# Laser_Teensy4save.net
KiCad netlist of a schematic drawn in EAGLE
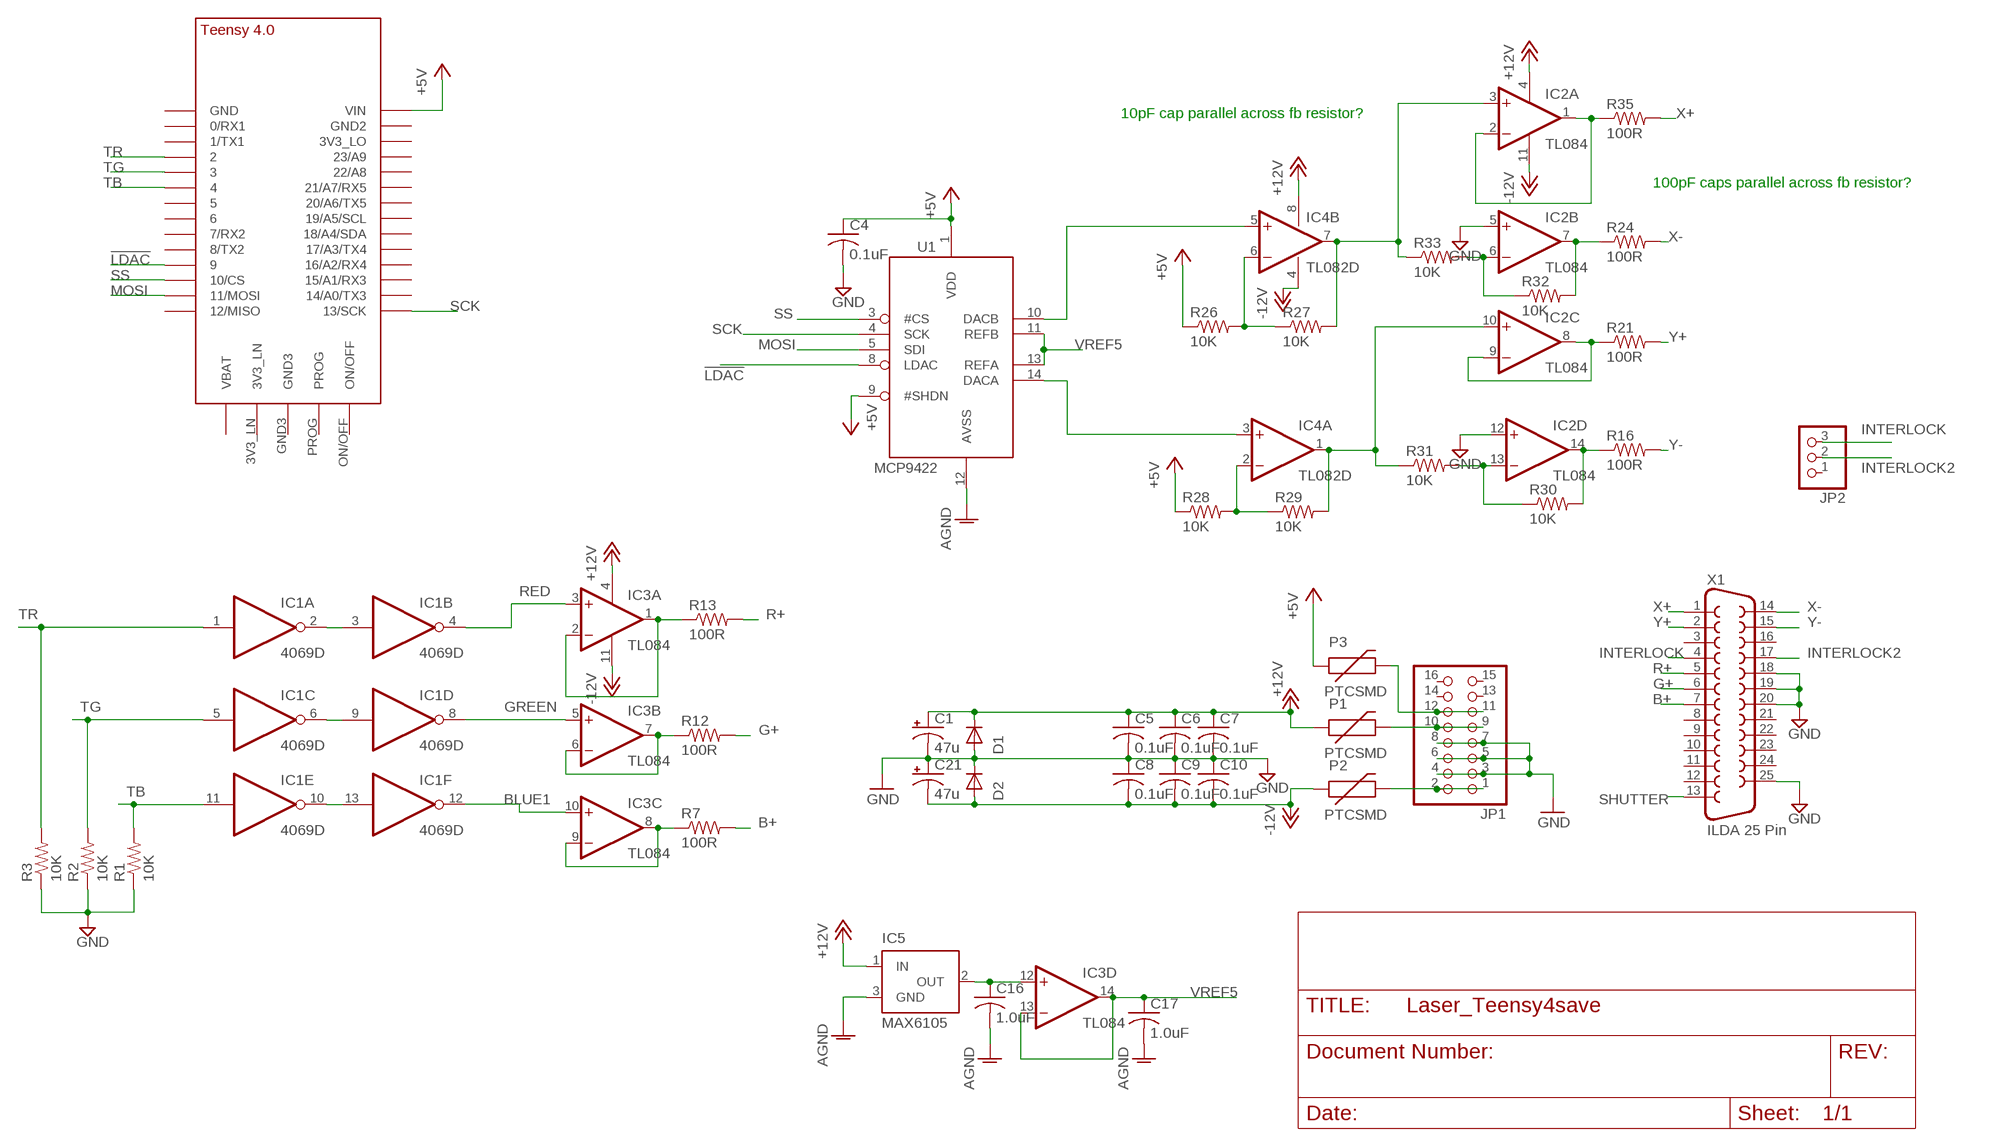
[diagram p0: schematic, sheet 1]

(export (version "E")
  (design (tool "Eeschema 10.0.6"))
  (components
    (comp (ref "C1")
      (value "47u")
      (footprint "eagle-import:PANASONIC_D")
      (libsource (lib "eagle-import") (part "CPOL-USD"))
    )
    (comp (ref "C4")
      (value "0.1uF")
      (footprint "eagle-import:C0603")
      (libsource (lib "eagle-import") (part "C-USC0603"))
    )
    (comp (ref "C5")
      (value "0.1uF")
      (footprint "eagle-import:C0603")
      (libsource (lib "eagle-import") (part "C-USC0603"))
    )
    (comp (ref "C6")
      (value "0.1uF")
      (footprint "eagle-import:C0603")
      (libsource (lib "eagle-import") (part "C-USC0603"))
    )
    (comp (ref "C7")
      (value "0.1uF")
      (footprint "eagle-import:C0603")
      (libsource (lib "eagle-import") (part "C-USC0603"))
    )
    (comp (ref "C8")
      (value "0.1uF")
      (footprint "eagle-import:C0603")
      (libsource (lib "eagle-import") (part "C-USC0603"))
    )
    (comp (ref "C9")
      (value "0.1uF")
      (footprint "eagle-import:C0603")
      (libsource (lib "eagle-import") (part "C-USC0603"))
    )
    (comp (ref "C10")
      (value "0.1uF")
      (footprint "eagle-import:C0603")
      (libsource (lib "eagle-import") (part "C-USC0603"))
    )
    (comp (ref "C16")
      (value "1.0uF")
      (footprint "eagle-import:C025-024X044")
      (libsource (lib "eagle-import") (part "C-US025-024X044"))
    )
    (comp (ref "C17")
      (value "1.0uF")
      (footprint "eagle-import:C025-024X044")
      (libsource (lib "eagle-import") (part "C-US025-024X044"))
    )
    (comp (ref "C21")
      (value "47u")
      (footprint "eagle-import:PANASONIC_D")
      (libsource (lib "eagle-import") (part "CPOL-USD"))
    )
    (comp (ref "D1")
      (value "1N5819HW")
      (footprint "eagle-import:SOD123")
      (libsource (lib "eagle-import") (part "DIODE-SOD123"))
    )
    (comp (ref "D2")
      (value "1N5819HW")
      (footprint "eagle-import:SOD123")
      (libsource (lib "eagle-import") (part "DIODE-SOD123"))
    )
    (comp (ref "IC1")
      (value "4069D")
      (footprint "eagle-import:SO14")
      (libsource (lib "eagle-import") (part "4069D"))
    )
    (comp (ref "IC2")
      (value "TL084")
      (footprint "eagle-import:SOIC-14")
      (libsource (lib "eagle-import") (part "TL084"))
    )
    (comp (ref "IC3")
      (value "TL084")
      (footprint "eagle-import:SOIC-14")
      (libsource (lib "eagle-import") (part "TL084"))
    )
    (comp (ref "IC4")
      (value "TL082D")
      (footprint "eagle-import:SO08")
      (libsource (lib "eagle-import") (part "TL082D"))
    )
    (comp (ref "IC5")
      (value "MAX6105")
      (footprint "eagle-import:SOT23")
      (libsource (lib "eagle-import") (part "MAX6520"))
    )
    (comp (ref "JP1")
      (value "PINHD-2X8")
      (footprint "eagle-import:2X08")
      (libsource (lib "eagle-import") (part "PINHD-2X8"))
    )
    (comp (ref "JP2")
      (value "PINHD-1X3")
      (footprint "eagle-import:1X03")
      (libsource (lib "eagle-import") (part "PINHD-1X3"))
    )
    (comp (ref "P1")
      (value "PTCSMD")
      (footprint "eagle-import:PTC-1206")
      (libsource (lib "eagle-import") (part "PTCSMD"))
    )
    (comp (ref "P2")
      (value "PTCSMD")
      (footprint "eagle-import:PTC-1206")
      (libsource (lib "eagle-import") (part "PTCSMD"))
    )
    (comp (ref "P3")
      (value "PTCSMD")
      (footprint "eagle-import:PTC-1206")
      (libsource (lib "eagle-import") (part "PTCSMD"))
    )
    (comp (ref "R1")
      (value "10K")
      (footprint "eagle-import:R0603")
      (libsource (lib "eagle-import") (part "R-US_R0603"))
    )
    (comp (ref "R2")
      (value "10K")
      (footprint "eagle-import:R0603")
      (libsource (lib "eagle-import") (part "R-US_R0603"))
    )
    (comp (ref "R3")
      (value "10K")
      (footprint "eagle-import:R0603")
      (libsource (lib "eagle-import") (part "R-US_R0603"))
    )
    (comp (ref "R7")
      (value "100R")
      (footprint "eagle-import:R0603")
      (libsource (lib "eagle-import") (part "R-US_R0603"))
    )
    (comp (ref "R12")
      (value "100R")
      (footprint "eagle-import:R0603")
      (libsource (lib "eagle-import") (part "R-US_R0603"))
    )
    (comp (ref "R13")
      (value "100R")
      (footprint "eagle-import:R0603")
      (libsource (lib "eagle-import") (part "R-US_R0603"))
    )
    (comp (ref "R16")
      (value "100R")
      (footprint "eagle-import:R0603")
      (libsource (lib "eagle-import") (part "R-US_R0603"))
    )
    (comp (ref "R21")
      (value "100R")
      (footprint "eagle-import:R0603")
      (libsource (lib "eagle-import") (part "R-US_R0603"))
    )
    (comp (ref "R24")
      (value "100R")
      (footprint "eagle-import:R0603")
      (libsource (lib "eagle-import") (part "R-US_R0603"))
    )
    (comp (ref "R26")
      (value "10K")
      (footprint "eagle-import:R0603")
      (libsource (lib "eagle-import") (part "R-US_R0603"))
    )
    (comp (ref "R27")
      (value "10K")
      (footprint "eagle-import:R0603")
      (libsource (lib "eagle-import") (part "R-US_R0603"))
    )
    (comp (ref "R28")
      (value "10K")
      (footprint "eagle-import:R0603")
      (libsource (lib "eagle-import") (part "R-US_R0603"))
    )
    (comp (ref "R29")
      (value "10K")
      (footprint "eagle-import:R0603")
      (libsource (lib "eagle-import") (part "R-US_R0603"))
    )
    (comp (ref "R30")
      (value "10K")
      (footprint "eagle-import:R0603")
      (libsource (lib "eagle-import") (part "R-US_R0603"))
    )
    (comp (ref "R31")
      (value "10K")
      (footprint "eagle-import:R0603")
      (libsource (lib "eagle-import") (part "R-US_R0603"))
    )
    (comp (ref "R32")
      (value "10K")
      (footprint "eagle-import:R0603")
      (libsource (lib "eagle-import") (part "R-US_R0603"))
    )
    (comp (ref "R33")
      (value "10K")
      (footprint "eagle-import:R0603")
      (libsource (lib "eagle-import") (part "R-US_R0603"))
    )
    (comp (ref "R35")
      (value "100R")
      (footprint "eagle-import:R0603")
      (libsource (lib "eagle-import") (part "R-US_R0603"))
    )
    (comp (ref "U$1")
      (value "TEENSY_4.0")
      (footprint "eagle-import:TEENSY_4.0")
      (libsource (lib "eagle-import") (part "TEENSY_4.0"))
    )
    (comp (ref "U1")
      (value "MCP4922")
      (footprint "eagle-import:SOIC-14")
      (libsource (lib "eagle-import") (part "MCP4922"))
    )
    (comp (ref "X1")
      (value "ILDA 25 Pin")
      (footprint "eagle-import:F25D")
      (libsource (lib "eagle-import") (part "F25D"))
    )
  )
  (nets
    (net (code "1") (name "+5V") (class "Default")
      (node (ref "C4") (pin "1") (pinfunction "1_1") (pintype "passive"))
      (node (ref "P3") (pin "1") (pinfunction "1_1") (pintype "bidirectional"))
      (node (ref "R26") (pin "1") (pinfunction "1_1") (pintype "passive"))
      (node (ref "R28") (pin "1") (pinfunction "1_1") (pintype "passive"))
      (node (ref "U$1") (pin "VIN") (pinfunction "VIN_VIN") (pintype "bidirectional"))
      (node (ref "U1") (pin "1") (pinfunction "VDD_1") (pintype "power_in"))
      (node (ref "U1") (pin "9") (pinfunction "#SHDN_9") (pintype "input"))
    )
    (net (code "2") (name "+12V") (class "Default")
      (node (ref "C1") (pin "+") (pinfunction "+_+") (pintype "passive"))
      (node (ref "C5") (pin "1") (pinfunction "1_1") (pintype "passive"))
      (node (ref "C6") (pin "1") (pinfunction "1_1") (pintype "passive"))
      (node (ref "C7") (pin "1") (pinfunction "1_1") (pintype "passive"))
      (node (ref "D1") (pin "C") (pinfunction "C_C") (pintype "passive"))
      (node (ref "IC2") (pin "4") (pinfunction "V+_4") (pintype "power_in"))
      (node (ref "IC3") (pin "4") (pinfunction "V+_4") (pintype "power_in"))
      (node (ref "IC4") (pin "8") (pinfunction "V+_8") (pintype "power_in"))
      (node (ref "IC5") (pin "1") (pinfunction "IN_1") (pintype "input"))
      (node (ref "P1") (pin "1") (pinfunction "1_1") (pintype "bidirectional"))
    )
    (net (code "3") (name "-12V") (class "Default")
      (node (ref "C10") (pin "2") (pinfunction "2_2") (pintype "passive"))
      (node (ref "C21") (pin "-") (pinfunction "-_-") (pintype "passive"))
      (node (ref "C8") (pin "2") (pinfunction "2_2") (pintype "passive"))
      (node (ref "C9") (pin "2") (pinfunction "2_2") (pintype "passive"))
      (node (ref "D2") (pin "A") (pinfunction "A_A") (pintype "passive"))
      (node (ref "IC2") (pin "11") (pinfunction "V-_11") (pintype "power_in"))
      (node (ref "IC3") (pin "11") (pinfunction "V-_11") (pintype "power_in"))
      (node (ref "IC4") (pin "4") (pinfunction "V-_4") (pintype "power_in"))
      (node (ref "P2") (pin "1") (pinfunction "1_1") (pintype "bidirectional"))
    )
    (net (code "4") (name "/B+") (class "Default")
      (node (ref "R7") (pin "2") (pinfunction "2_2") (pintype "passive"))
      (node (ref "X1") (pin "7") (pinfunction "7_7") (pintype "passive"))
    )
    (net (code "5") (name "/BLUE1") (class "Default")
      (node (ref "IC1") (pin "12") (pinfunction "O_12") (pintype "output"))
      (node (ref "IC3") (pin "10") (pinfunction "+IN_10") (pintype "input"))
    )
    (net (code "6") (name "/G+") (class "Default")
      (node (ref "R12") (pin "2") (pinfunction "2_2") (pintype "passive"))
      (node (ref "X1") (pin "6") (pinfunction "6_6") (pintype "passive"))
    )
    (net (code "7") (name "/GREEN") (class "Default")
      (node (ref "IC1") (pin "8") (pinfunction "O_8") (pintype "output"))
      (node (ref "IC3") (pin "5") (pinfunction "+IN_5") (pintype "input"))
    )
    (net (code "8") (name "/INTERLOCK") (class "Default")
      (node (ref "JP2") (pin "3") (pinfunction "3_3") (pintype "passive"))
      (node (ref "X1") (pin "4") (pinfunction "4_4") (pintype "passive"))
    )
    (net (code "9") (name "/INTERLOCK2") (class "Default")
      (node (ref "JP2") (pin "2") (pinfunction "2_2") (pintype "passive"))
      (node (ref "X1") (pin "17") (pinfunction "17_17") (pintype "passive"))
    )
    (net (code "10") (name "/MOSI") (class "Default")
      (node (ref "U$1") (pin "11/MOSI") (pinfunction "11/MOSI_11/MOSI") (pintype "bidirectional"))
      (node (ref "U1") (pin "5") (pinfunction "SDI_5") (pintype "input"))
    )
    (net (code "11") (name "/R+") (class "Default")
      (node (ref "R13") (pin "2") (pinfunction "2_2") (pintype "passive"))
      (node (ref "X1") (pin "5") (pinfunction "5_5") (pintype "passive"))
    )
    (net (code "12") (name "/RED") (class "Default")
      (node (ref "IC1") (pin "4") (pinfunction "O_4") (pintype "output"))
      (node (ref "IC3") (pin "3") (pinfunction "+IN_3") (pintype "input"))
    )
    (net (code "13") (name "/SCK") (class "Default")
      (node (ref "U$1") (pin "13/SCK") (pinfunction "13/SCK_13/SCK") (pintype "bidirectional"))
      (node (ref "U1") (pin "4") (pinfunction "SCK_4") (pintype "input"))
    )
    (net (code "14") (name "/SHUTTER") (class "Default")
      (node (ref "X1") (pin "13") (pinfunction "13_13") (pintype "passive"))
    )
    (net (code "15") (name "/SS") (class "Default")
      (node (ref "U$1") (pin "10/CS") (pinfunction "10/CS_10/CS") (pintype "bidirectional"))
      (node (ref "U1") (pin "3") (pinfunction "#CS_3") (pintype "input"))
    )
    (net (code "16") (name "/TB") (class "Default")
      (node (ref "IC1") (pin "11") (pinfunction "I_11") (pintype "input"))
      (node (ref "R1") (pin "2") (pinfunction "2_2") (pintype "passive"))
      (node (ref "U$1") (pin "4/CANRX") (pinfunction "4_4/CANRX") (pintype "bidirectional"))
    )
    (net (code "17") (name "/TG") (class "Default")
      (node (ref "IC1") (pin "5") (pinfunction "I_5") (pintype "input"))
      (node (ref "R2") (pin "2") (pinfunction "2_2") (pintype "passive"))
      (node (ref "U$1") (pin "3/CANTX") (pinfunction "3_3/CANTX") (pintype "bidirectional"))
    )
    (net (code "18") (name "/TR") (class "Default")
      (node (ref "IC1") (pin "1") (pinfunction "I_1") (pintype "input"))
      (node (ref "R3") (pin "2") (pinfunction "2_2") (pintype "passive"))
      (node (ref "U$1") (pin "2") (pinfunction "2_2") (pintype "bidirectional"))
    )
    (net (code "19") (name "/VREF5") (class "Default")
      (node (ref "C17") (pin "1") (pinfunction "1_1") (pintype "passive"))
      (node (ref "IC3") (pin "13") (pinfunction "-IN_13") (pintype "input"))
      (node (ref "IC3") (pin "14") (pinfunction "OUT_14") (pintype "output"))
      (node (ref "U1") (pin "11") (pinfunction "REFB_11") (pintype "input"))
      (node (ref "U1") (pin "13") (pinfunction "REFA_13") (pintype "input"))
    )
    (net (code "20") (name "/X+") (class "Default")
      (node (ref "R35") (pin "2") (pinfunction "2_2") (pintype "passive"))
      (node (ref "X1") (pin "1") (pinfunction "1_1") (pintype "passive"))
    )
    (net (code "21") (name "/X-") (class "Default")
      (node (ref "R24") (pin "2") (pinfunction "2_2") (pintype "passive"))
      (node (ref "X1") (pin "14") (pinfunction "14_14") (pintype "passive"))
    )
    (net (code "22") (name "/Y+") (class "Default")
      (node (ref "R21") (pin "2") (pinfunction "2_2") (pintype "passive"))
      (node (ref "X1") (pin "2") (pinfunction "2_2") (pintype "passive"))
    )
    (net (code "23") (name "/Y-") (class "Default")
      (node (ref "R16") (pin "2") (pinfunction "2_2") (pintype "passive"))
      (node (ref "X1") (pin "15") (pinfunction "15_15") (pintype "passive"))
    )
    (net (code "24") (name "/~{LDAC}") (class "Default")
      (node (ref "U$1") (pin "9/CS") (pinfunction "9_9/CS") (pintype "bidirectional"))
      (node (ref "U1") (pin "8") (pinfunction "LDAC_8") (pintype "input"))
    )
    (net (code "25") (name "AGND") (class "Default")
      (node (ref "C16") (pin "2") (pinfunction "2_2") (pintype "passive"))
      (node (ref "C17") (pin "2") (pinfunction "2_2") (pintype "passive"))
      (node (ref "IC5") (pin "3") (pinfunction "GND_3") (pintype "power_in"))
      (node (ref "U1") (pin "12") (pinfunction "AVSS_12") (pintype "power_in"))
    )
    (net (code "26") (name "GND") (class "Default")
      (node (ref "C1") (pin "-") (pinfunction "-_-") (pintype "passive"))
      (node (ref "C10") (pin "1") (pinfunction "1_1") (pintype "passive"))
      (node (ref "C21") (pin "+") (pinfunction "+_+") (pintype "passive"))
      (node (ref "C4") (pin "2") (pinfunction "2_2") (pintype "passive"))
      (node (ref "C5") (pin "2") (pinfunction "2_2") (pintype "passive"))
      (node (ref "C6") (pin "2") (pinfunction "2_2") (pintype "passive"))
      (node (ref "C7") (pin "2") (pinfunction "2_2") (pintype "passive"))
      (node (ref "C8") (pin "1") (pinfunction "1_1") (pintype "passive"))
      (node (ref "C9") (pin "1") (pinfunction "1_1") (pintype "passive"))
      (node (ref "D1") (pin "A") (pinfunction "A_A") (pintype "passive"))
      (node (ref "D2") (pin "C") (pinfunction "C_C") (pintype "passive"))
      (node (ref "IC2") (pin "12") (pinfunction "+IN_12") (pintype "input"))
      (node (ref "IC2") (pin "5") (pinfunction "+IN_5") (pintype "input"))
      (node (ref "JP1") (pin "3") (pinfunction "3_3") (pintype "passive"))
      (node (ref "JP1") (pin "4") (pinfunction "4_4") (pintype "passive"))
      (node (ref "JP1") (pin "5") (pinfunction "5_5") (pintype "passive"))
      (node (ref "JP1") (pin "6") (pinfunction "6_6") (pintype "passive"))
      (node (ref "JP1") (pin "7") (pinfunction "7_7") (pintype "passive"))
      (node (ref "JP1") (pin "8") (pinfunction "8_8") (pintype "passive"))
      (node (ref "R1") (pin "1") (pinfunction "1_1") (pintype "passive"))
      (node (ref "R2") (pin "1") (pinfunction "1_1") (pintype "passive"))
      (node (ref "R3") (pin "1") (pinfunction "1_1") (pintype "passive"))
      (node (ref "X1") (pin "18") (pinfunction "18_18") (pintype "passive"))
      (node (ref "X1") (pin "19") (pinfunction "19_19") (pintype "passive"))
      (node (ref "X1") (pin "20") (pinfunction "20_20") (pintype "passive"))
      (node (ref "X1") (pin "25") (pinfunction "25_25") (pintype "passive"))
    )
    (net (code "27") (name "Net-(IC1A-O)") (class "Default")
      (node (ref "IC1") (pin "2") (pinfunction "O_2") (pintype "output"))
      (node (ref "IC1") (pin "3") (pinfunction "I_3") (pintype "input"))
    )
    (net (code "28") (name "Net-(IC1C-O)") (class "Default")
      (node (ref "IC1") (pin "6") (pinfunction "O_6") (pintype "output"))
      (node (ref "IC1") (pin "9") (pinfunction "I_9") (pintype "input"))
    )
    (net (code "29") (name "Net-(IC1E-O)") (class "Default")
      (node (ref "IC1") (pin "10") (pinfunction "O_10") (pintype "output"))
      (node (ref "IC1") (pin "13") (pinfunction "I_13") (pintype "input"))
    )
    (net (code "30") (name "Net-(IC2A-+IN)") (class "Default")
      (node (ref "IC2") (pin "3") (pinfunction "+IN_3") (pintype "input"))
      (node (ref "IC4") (pin "7") (pinfunction "OUT_7") (pintype "output"))
      (node (ref "R27") (pin "2") (pinfunction "2_2") (pintype "passive"))
      (node (ref "R33") (pin "1") (pinfunction "1_1") (pintype "passive"))
    )
    (net (code "31") (name "Net-(IC2A--IN)") (class "Default")
      (node (ref "IC2") (pin "1") (pinfunction "OUT_1") (pintype "output"))
      (node (ref "IC2") (pin "2") (pinfunction "-IN_2") (pintype "input"))
      (node (ref "R35") (pin "1") (pinfunction "1_1") (pintype "passive"))
    )
    (net (code "32") (name "Net-(IC2B--IN)") (class "Default")
      (node (ref "IC2") (pin "6") (pinfunction "-IN_6") (pintype "input"))
      (node (ref "R32") (pin "1") (pinfunction "1_1") (pintype "passive"))
      (node (ref "R33") (pin "2") (pinfunction "2_2") (pintype "passive"))
    )
    (net (code "33") (name "Net-(IC2B-OUT)") (class "Default")
      (node (ref "IC2") (pin "7") (pinfunction "OUT_7") (pintype "output"))
      (node (ref "R24") (pin "1") (pinfunction "1_1") (pintype "passive"))
      (node (ref "R32") (pin "2") (pinfunction "2_2") (pintype "passive"))
    )
    (net (code "34") (name "Net-(IC2C-+IN)") (class "Default")
      (node (ref "IC2") (pin "10") (pinfunction "+IN_10") (pintype "input"))
      (node (ref "IC4") (pin "1") (pinfunction "OUT_1") (pintype "output"))
      (node (ref "R29") (pin "2") (pinfunction "2_2") (pintype "passive"))
      (node (ref "R31") (pin "1") (pinfunction "1_1") (pintype "passive"))
    )
    (net (code "35") (name "Net-(IC2C--IN)") (class "Default")
      (node (ref "IC2") (pin "8") (pinfunction "OUT_8") (pintype "output"))
      (node (ref "IC2") (pin "9") (pinfunction "-IN_9") (pintype "input"))
      (node (ref "R21") (pin "1") (pinfunction "1_1") (pintype "passive"))
    )
    (net (code "36") (name "Net-(IC2D--IN)") (class "Default")
      (node (ref "IC2") (pin "13") (pinfunction "-IN_13") (pintype "input"))
      (node (ref "R30") (pin "1") (pinfunction "1_1") (pintype "passive"))
      (node (ref "R31") (pin "2") (pinfunction "2_2") (pintype "passive"))
    )
    (net (code "37") (name "Net-(IC2D-OUT)") (class "Default")
      (node (ref "IC2") (pin "14") (pinfunction "OUT_14") (pintype "output"))
      (node (ref "R16") (pin "1") (pinfunction "1_1") (pintype "passive"))
      (node (ref "R30") (pin "2") (pinfunction "2_2") (pintype "passive"))
    )
    (net (code "38") (name "Net-(IC3A--IN)") (class "Default")
      (node (ref "IC3") (pin "1") (pinfunction "OUT_1") (pintype "output"))
      (node (ref "IC3") (pin "2") (pinfunction "-IN_2") (pintype "input"))
      (node (ref "R13") (pin "1") (pinfunction "1_1") (pintype "passive"))
    )
    (net (code "39") (name "Net-(IC3B--IN)") (class "Default")
      (node (ref "IC3") (pin "6") (pinfunction "-IN_6") (pintype "input"))
      (node (ref "IC3") (pin "7") (pinfunction "OUT_7") (pintype "output"))
      (node (ref "R12") (pin "1") (pinfunction "1_1") (pintype "passive"))
    )
    (net (code "40") (name "Net-(IC3C--IN)") (class "Default")
      (node (ref "IC3") (pin "8") (pinfunction "OUT_8") (pintype "output"))
      (node (ref "IC3") (pin "9") (pinfunction "-IN_9") (pintype "input"))
      (node (ref "R7") (pin "1") (pinfunction "1_1") (pintype "passive"))
    )
    (net (code "41") (name "Net-(IC3D-+IN)") (class "Default")
      (node (ref "C16") (pin "1") (pinfunction "1_1") (pintype "passive"))
      (node (ref "IC3") (pin "12") (pinfunction "+IN_12") (pintype "input"))
      (node (ref "IC5") (pin "2") (pinfunction "OUT_2") (pintype "input"))
    )
    (net (code "42") (name "Net-(IC4A-+IN)") (class "Default")
      (node (ref "IC4") (pin "3") (pinfunction "+IN_3") (pintype "input"))
      (node (ref "U1") (pin "14") (pinfunction "DACA_14") (pintype "output"))
    )
    (net (code "43") (name "Net-(IC4A--IN)") (class "Default")
      (node (ref "IC4") (pin "2") (pinfunction "-IN_2") (pintype "input"))
      (node (ref "R28") (pin "2") (pinfunction "2_2") (pintype "passive"))
      (node (ref "R29") (pin "1") (pinfunction "1_1") (pintype "passive"))
    )
    (net (code "44") (name "Net-(IC4B-+IN)") (class "Default")
      (node (ref "IC4") (pin "5") (pinfunction "+IN_5") (pintype "input"))
      (node (ref "U1") (pin "10") (pinfunction "DACB_10") (pintype "output"))
    )
    (net (code "45") (name "Net-(IC4B--IN)") (class "Default")
      (node (ref "IC4") (pin "6") (pinfunction "-IN_6") (pintype "input"))
      (node (ref "R26") (pin "2") (pinfunction "2_2") (pintype "passive"))
      (node (ref "R27") (pin "1") (pinfunction "1_1") (pintype "passive"))
    )
    (net (code "46") (name "Net-(JP1-Pad1)") (class "Default")
      (node (ref "JP1") (pin "1") (pinfunction "1_1") (pintype "passive"))
      (node (ref "JP1") (pin "2") (pinfunction "2_2") (pintype "passive"))
      (node (ref "P2") (pin "2") (pinfunction "2_2") (pintype "bidirectional"))
    )
    (net (code "47") (name "Net-(JP1-Pad10)") (class "Default")
      (node (ref "JP1") (pin "10") (pinfunction "10_10") (pintype "passive"))
      (node (ref "JP1") (pin "9") (pinfunction "9_9") (pintype "passive"))
      (node (ref "P1") (pin "2") (pinfunction "2_2") (pintype "bidirectional"))
    )
    (net (code "48") (name "Net-(JP1-Pad11)") (class "Default")
      (node (ref "JP1") (pin "11") (pinfunction "11_11") (pintype "passive"))
      (node (ref "JP1") (pin "12") (pinfunction "12_12") (pintype "passive"))
      (node (ref "P3") (pin "2") (pinfunction "2_2") (pintype "bidirectional"))
    )
    (net (code "49") (name "unconnected-(JP1-Pad13)") (class "Default")
      (node (ref "JP1") (pin "13") (pinfunction "13_13") (pintype "passive"))
    )
    (net (code "50") (name "unconnected-(JP1-Pad14)") (class "Default")
      (node (ref "JP1") (pin "14") (pinfunction "14_14") (pintype "passive"))
    )
    (net (code "51") (name "unconnected-(JP1-Pad15)") (class "Default")
      (node (ref "JP1") (pin "15") (pinfunction "15_15") (pintype "passive"))
    )
    (net (code "52") (name "unconnected-(JP1-Pad16)") (class "Default")
      (node (ref "JP1") (pin "16") (pinfunction "16_16") (pintype "passive"))
    )
    (net (code "53") (name "unconnected-(JP2-Pad1)") (class "Default")
      (node (ref "JP2") (pin "1") (pinfunction "1_1") (pintype "passive"))
    )
    (net (code "54") (name "unconnected-(U$1-0{slash}RX1-Pad0{slash}RX)") (class "Default")
      (node (ref "U$1") (pin "0/RX") (pinfunction "0/RX1_0/RX") (pintype "bidirectional"))
    )
    (net (code "55") (name "unconnected-(U$1-1{slash}TX1-Pad1{slash}TX)") (class "Default")
      (node (ref "U$1") (pin "1/TX") (pinfunction "1/TX1_1/TX") (pintype "bidirectional"))
    )
    (net (code "56") (name "unconnected-(U$1-7{slash}RX2-Pad7)") (class "Default")
      (node (ref "U$1") (pin "7") (pinfunction "7/RX2_7") (pintype "bidirectional"))
    )
    (net (code "57") (name "unconnected-(U$1-8{slash}TX2-Pad8)") (class "Default")
      (node (ref "U$1") (pin "8") (pinfunction "8/TX2_8") (pintype "bidirectional"))
    )
    (net (code "58") (name "unconnected-(U$1-14{slash}A0{slash}TX3-Pad14{slash}A0)") (class "Default")
      (node (ref "U$1") (pin "14/A0") (pinfunction "14/A0/TX3_14/A0") (pintype "bidirectional"))
    )
    (net (code "59") (name "unconnected-(U$1-15{slash}A1{slash}RX3-Pad15{slash}A1)") (class "Default")
      (node (ref "U$1") (pin "15/A1") (pinfunction "15/A1/RX3_15/A1") (pintype "bidirectional"))
    )
    (net (code "60") (name "unconnected-(U$1-16{slash}A2{slash}RX4-Pad16{slash}A2)") (class "Default")
      (node (ref "U$1") (pin "16/A2") (pinfunction "16/A2/RX4_16/A2") (pintype "bidirectional"))
    )
    (net (code "61") (name "unconnected-(U$1-17{slash}A3{slash}TX4-Pad17{slash}A3)") (class "Default")
      (node (ref "U$1") (pin "17/A3") (pinfunction "17/A3/TX4_17/A3") (pintype "bidirectional"))
    )
    (net (code "62") (name "unconnected-(U$1-20{slash}A6{slash}TX5-Pad20{slash}A6)") (class "Default")
      (node (ref "U$1") (pin "20/A6") (pinfunction "20/A6/TX5_20/A6") (pintype "bidirectional"))
    )
    (net (code "63") (name "unconnected-(U$1-21{slash}A7{slash}RX5-Pad21{slash}A7)") (class "Default")
      (node (ref "U$1") (pin "21/A7") (pinfunction "21/A7/RX5_21/A7") (pintype "bidirectional"))
    )
    (net (code "64") (name "unconnected-(U$1-Pad3V3_LN)") (class "Default")
      (node (ref "U$1") (pin "3V3_LN") (pinfunction "3V3_LN_3V3_LN") (pintype "bidirectional"))
    )
    (net (code "65") (name "unconnected-(U$1-Pad3V3_LO)") (class "Default")
      (node (ref "U$1") (pin "3V3_LO") (pinfunction "3V3_LO_3V3_LO") (pintype "bidirectional"))
    )
    (net (code "66") (name "unconnected-(U$1-Pad5)") (class "Default")
      (node (ref "U$1") (pin "5") (pinfunction "5_5") (pintype "bidirectional"))
    )
    (net (code "67") (name "unconnected-(U$1-Pad6)") (class "Default")
      (node (ref "U$1") (pin "6") (pinfunction "6_6") (pintype "bidirectional"))
    )
    (net (code "68") (name "unconnected-(U$1-Pad12{slash}MISO)") (class "Default")
      (node (ref "U$1") (pin "12/MISO") (pinfunction "12/MISO_12/MISO") (pintype "bidirectional"))
    )
    (net (code "69") (name "unconnected-(U$1-Pad18{slash}A4{slash}SDA)") (class "Default")
      (node (ref "U$1") (pin "18/A4/SDA") (pinfunction "18/A4/SDA_18/A4/SDA") (pintype "bidirectional"))
    )
    (net (code "70") (name "unconnected-(U$1-Pad19{slash}A5{slash}SCL)") (class "Default")
      (node (ref "U$1") (pin "19/A5/SCL") (pinfunction "19/A5/SCL_19/A5/SCL") (pintype "bidirectional"))
    )
    (net (code "71") (name "unconnected-(U$1-Pad22{slash}A8)") (class "Default")
      (node (ref "U$1") (pin "22/A8") (pinfunction "22/A8_22/A8") (pintype "bidirectional"))
    )
    (net (code "72") (name "unconnected-(U$1-Pad23{slash}A9)") (class "Default")
      (node (ref "U$1") (pin "23/A9") (pinfunction "23/A9_23/A9") (pintype "bidirectional"))
    )
    (net (code "73") (name "unconnected-(U$1-PadGND)") (class "Default")
      (node (ref "U$1") (pin "GND") (pinfunction "GND_GND") (pintype "bidirectional"))
    )
    (net (code "74") (name "unconnected-(U$1-PadGND2)") (class "Default")
      (node (ref "U$1") (pin "GND2") (pinfunction "GND2_GND2") (pintype "bidirectional"))
    )
    (net (code "75") (name "unconnected-(U$1-PadGND3)") (class "Default")
      (node (ref "U$1") (pin "GND3") (pinfunction "GND3_GND3") (pintype "bidirectional"))
    )
    (net (code "76") (name "unconnected-(U$1-PadON{slash}OFF)") (class "Default")
      (node (ref "U$1") (pin "ON/OFF") (pinfunction "ON/OFF_ON/OFF") (pintype "bidirectional"))
    )
    (net (code "77") (name "unconnected-(U$1-PadPROG)") (class "Default")
      (node (ref "U$1") (pin "PROG") (pinfunction "PROG_PROG") (pintype "bidirectional"))
    )
    (net (code "78") (name "unconnected-(U$1-VBAT-PadVBAT\\)") (class "Default")
      (node (ref "U$1") (pin "VBAT\\") (pinfunction "VBAT_VBAT\\") (pintype "bidirectional"))
    )
    (net (code "79") (name "unconnected-(X1-Pad3)") (class "Default")
      (node (ref "X1") (pin "3") (pinfunction "3_3") (pintype "passive"))
    )
    (net (code "80") (name "unconnected-(X1-Pad8)") (class "Default")
      (node (ref "X1") (pin "8") (pinfunction "8_8") (pintype "passive"))
    )
    (net (code "81") (name "unconnected-(X1-Pad9)") (class "Default")
      (node (ref "X1") (pin "9") (pinfunction "9_9") (pintype "passive"))
    )
    (net (code "82") (name "unconnected-(X1-Pad10)") (class "Default")
      (node (ref "X1") (pin "10") (pinfunction "10_10") (pintype "passive"))
    )
    (net (code "83") (name "unconnected-(X1-Pad11)") (class "Default")
      (node (ref "X1") (pin "11") (pinfunction "11_11") (pintype "passive"))
    )
    (net (code "84") (name "unconnected-(X1-Pad12)") (class "Default")
      (node (ref "X1") (pin "12") (pinfunction "12_12") (pintype "passive"))
    )
    (net (code "85") (name "unconnected-(X1-Pad16)") (class "Default")
      (node (ref "X1") (pin "16") (pinfunction "16_16") (pintype "passive"))
    )
    (net (code "86") (name "unconnected-(X1-Pad21)") (class "Default")
      (node (ref "X1") (pin "21") (pinfunction "21_21") (pintype "passive"))
    )
    (net (code "87") (name "unconnected-(X1-Pad22)") (class "Default")
      (node (ref "X1") (pin "22") (pinfunction "22_22") (pintype "passive"))
    )
    (net (code "88") (name "unconnected-(X1-Pad23)") (class "Default")
      (node (ref "X1") (pin "23") (pinfunction "23_23") (pintype "passive"))
    )
    (net (code "89") (name "unconnected-(X1-Pad24)") (class "Default")
      (node (ref "X1") (pin "24") (pinfunction "24_24") (pintype "passive"))
    )
  )
)
